# motorController.net
KiCad netlist of a schematic drawn in Altium Designer
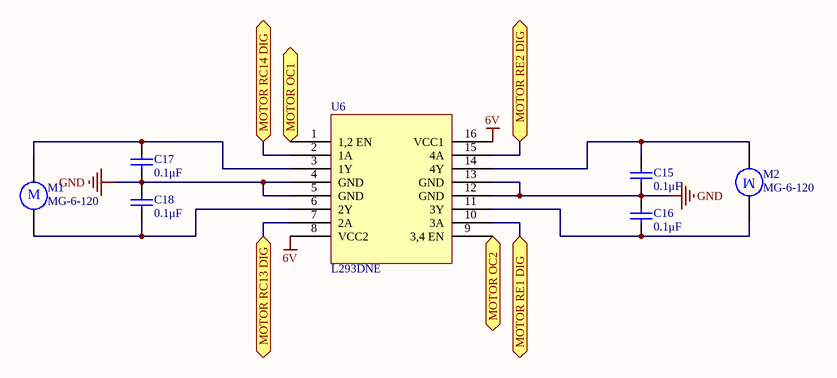
[diagram p0: motorController.SchDoc]

(export (version "E")
  (design (tool "Eeschema 10.0.6"))
  (components
    (comp (ref "C15")
      (value "0.1μF")
      (footprint "capacitor")
      (description "Capacitor")
      (fields (field (name "PUBLISHER") "Altium Limited"))
      (libsource (lib "Miscellaneous Devices") (part "Cap"))
    )
    (comp (ref "C16")
      (value "0.1μF")
      (footprint "capacitor")
      (description "Capacitor")
      (fields (field (name "PUBLISHER") "Altium Limited"))
      (libsource (lib "Miscellaneous Devices") (part "Cap"))
    )
    (comp (ref "C17")
      (value "0.1μF")
      (footprint "capacitor")
      (description "Capacitor")
      (fields (field (name "PUBLISHER") "Altium Limited"))
      (libsource (lib "Miscellaneous Devices") (part "Cap"))
    )
    (comp (ref "C18")
      (value "0.1μF")
      (footprint "capacitor")
      (description "Capacitor")
      (fields (field (name "PUBLISHER") "Altium Limited"))
      (libsource (lib "Miscellaneous Devices") (part "Cap"))
    )
    (comp (ref "M1")
      (value "MG-6-120")
      (footprint "Motor2")
      (description "Motor, General Kind")
      (fields (field (name "PUBLISHER") "Altium Limited"))
      (libsource (lib "Miscellaneous Devices") (part "Motor"))
    )
    (comp (ref "M2")
      (value "MG-6-120")
      (footprint "Motor2")
      (description "Motor, General Kind")
      (fields (field (name "PUBLISHER") "Altium Limited"))
      (libsource (lib "Miscellaneous Devices") (part "Motor"))
    )
    (comp (ref "U6")
      (value "L293DNE")
      (footprint "MotorDriver")
      (libsource (lib "PROBOT_Schema_Library") (part "Motor Driver"))
    )
  )
  (nets
    (net (code "1") (name "/MOTOR OC1") (class "Default")
      (node (ref "U6") (pin "1") (pinfunction "1,2_EN_1") (pintype "passive"))
    )
    (net (code "2") (name "/MOTOR OC2") (class "Default")
      (node (ref "U6") (pin "9") (pinfunction "3,4_EN_9") (pintype "passive"))
    )
    (net (code "3") (name "/MOTOR RC13 DIG") (class "Default")
      (node (ref "U6") (pin "7") (pinfunction "2A_7") (pintype "passive"))
    )
    (net (code "4") (name "/MOTOR RC14 DIG") (class "Default")
      (node (ref "U6") (pin "2") (pinfunction "1A_2") (pintype "passive"))
    )
    (net (code "5") (name "/MOTOR RE1 DIG") (class "Default")
      (node (ref "U6") (pin "10") (pinfunction "3A_10") (pintype "passive"))
    )
    (net (code "6") (name "/MOTOR RE2 DIG") (class "Default")
      (node (ref "U6") (pin "15") (pinfunction "4A_15") (pintype "passive"))
    )
    (net (code "7") (name "6V") (class "Default")
      (node (ref "U6") (pin "16") (pinfunction "VCC1_16") (pintype "passive"))
      (node (ref "U6") (pin "8") (pinfunction "VCC2_8") (pintype "passive"))
    )
    (net (code "8") (name "GND") (class "Default")
      (node (ref "C15") (pin "2") (pinfunction "2_2") (pintype "passive"))
      (node (ref "C16") (pin "1") (pinfunction "1_1") (pintype "passive"))
      (node (ref "C17") (pin "1") (pinfunction "1_1") (pintype "passive"))
      (node (ref "C18") (pin "2") (pinfunction "2_2") (pintype "passive"))
      (node (ref "U6") (pin "12") (pinfunction "GND_12") (pintype "passive"))
      (node (ref "U6") (pin "13") (pinfunction "GND_13") (pintype "passive"))
      (node (ref "U6") (pin "4") (pinfunction "GND_4") (pintype "passive"))
      (node (ref "U6") (pin "5") (pinfunction "GND_5") (pintype "passive"))
    )
    (net (code "9") (name "Net-(U6-1Y)") (class "Default")
      (node (ref "C17") (pin "2") (pinfunction "2_2") (pintype "passive"))
      (node (ref "M1") (pin "1") (pinfunction "1_1") (pintype "passive"))
      (node (ref "U6") (pin "3") (pinfunction "1Y_3") (pintype "passive"))
    )
    (net (code "10") (name "Net-(U6-2Y)") (class "Default")
      (node (ref "C18") (pin "1") (pinfunction "1_1") (pintype "passive"))
      (node (ref "M1") (pin "2") (pinfunction "2_2") (pintype "passive"))
      (node (ref "U6") (pin "6") (pinfunction "2Y_6") (pintype "passive"))
    )
    (net (code "11") (name "Net-(U6-3Y)") (class "Default")
      (node (ref "C16") (pin "2") (pinfunction "2_2") (pintype "passive"))
      (node (ref "M2") (pin "1") (pinfunction "1_1") (pintype "passive"))
      (node (ref "U6") (pin "11") (pinfunction "3Y_11") (pintype "passive"))
    )
    (net (code "12") (name "Net-(U6-4Y)") (class "Default")
      (node (ref "C15") (pin "1") (pinfunction "1_1") (pintype "passive"))
      (node (ref "M2") (pin "2") (pinfunction "2_2") (pintype "passive"))
      (node (ref "U6") (pin "14") (pinfunction "4Y_14") (pintype "passive"))
    )
  )
)
